# digital_warrior_v02.net
KiCad netlist of a schematic drawn in EAGLE
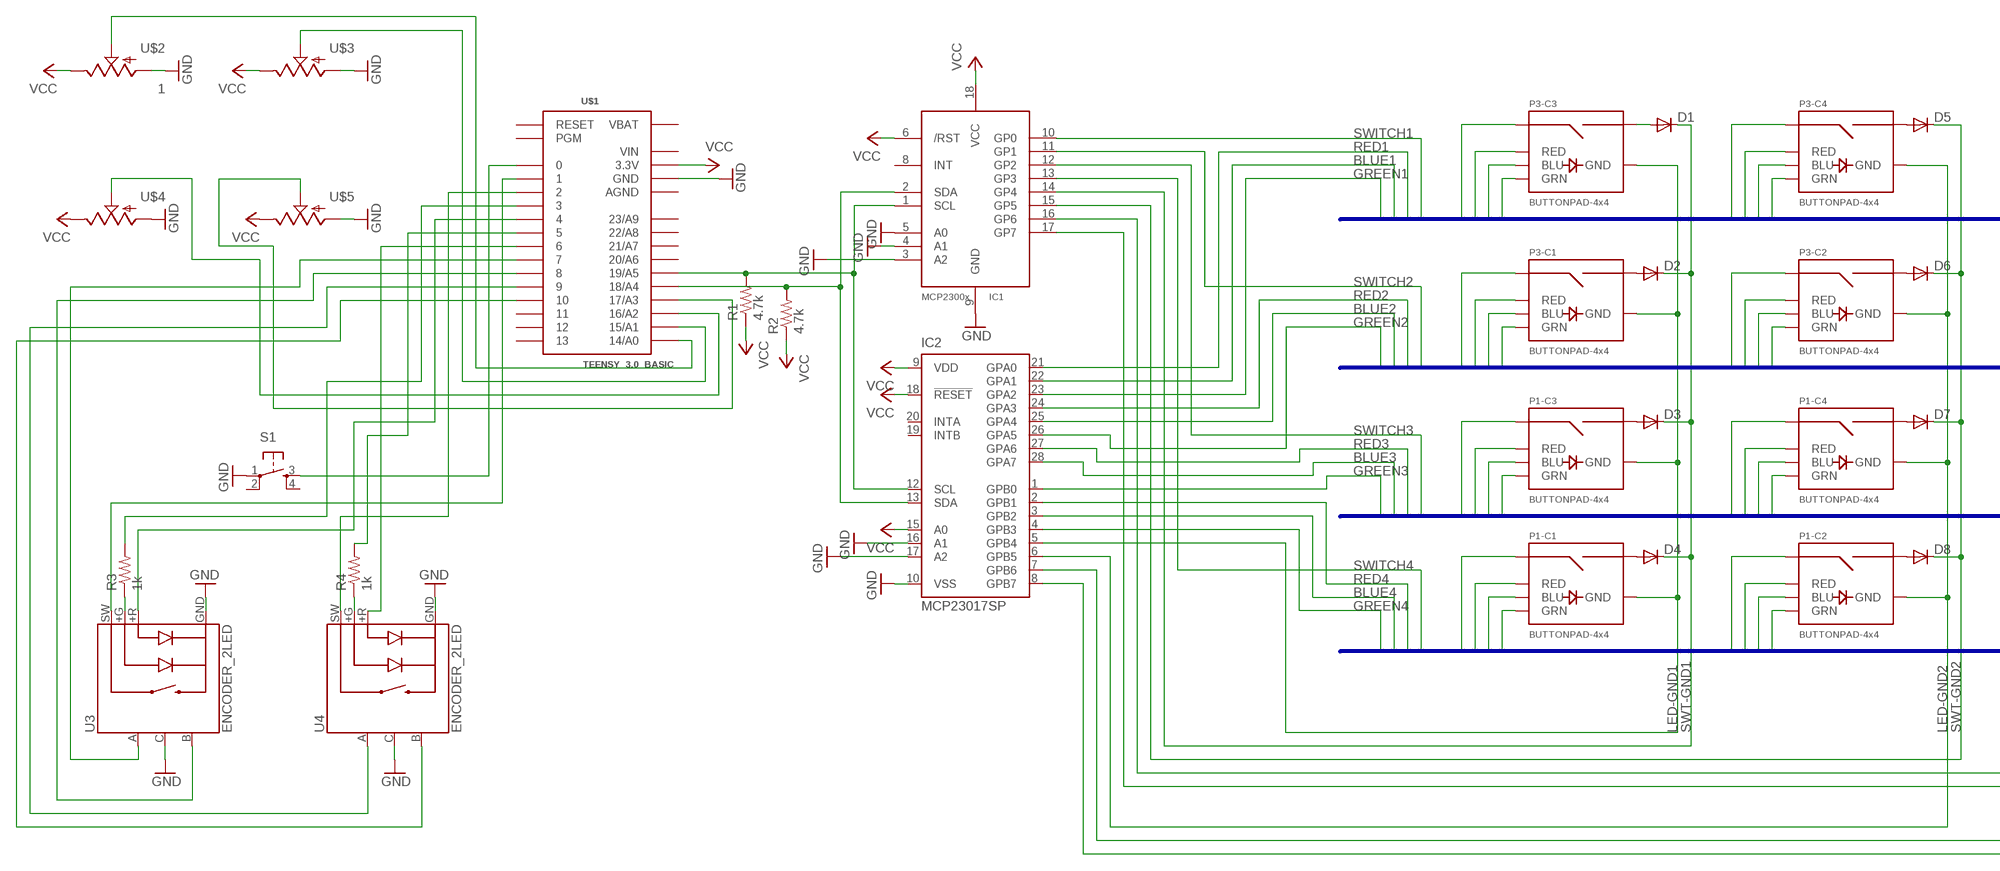
[diagram p0: schematic, sheet 1, part 1 of 2]
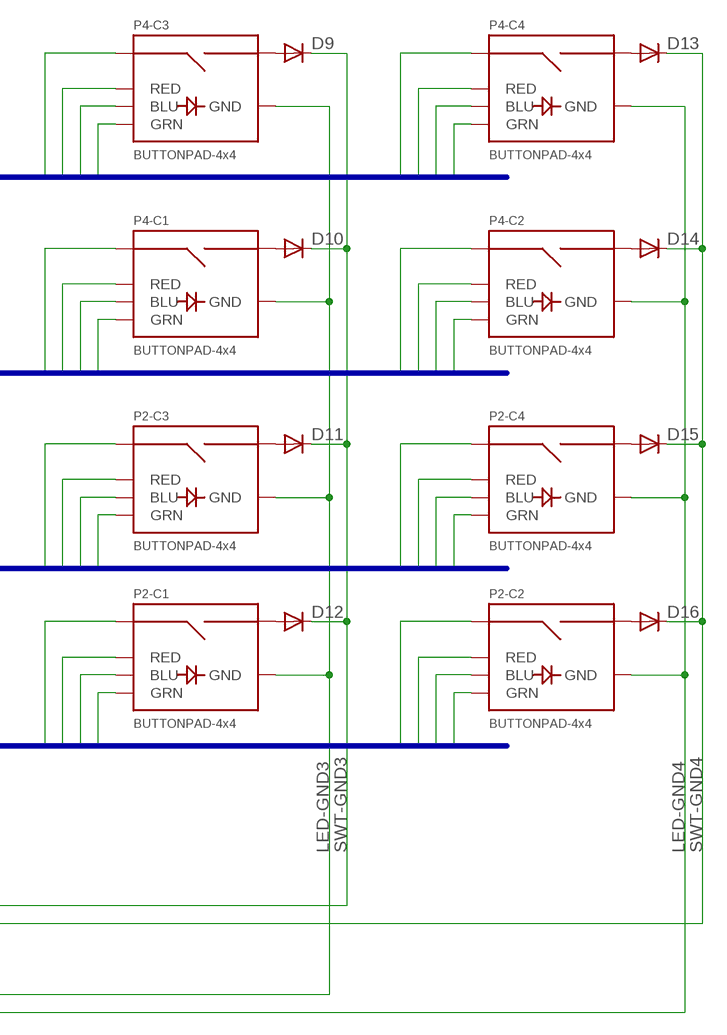
[diagram p1: schematic, sheet 1, part 2 of 2]

(export (version "E")
  (design (tool "Eeschema 10.0.6"))
  (components
    (comp (ref "D1")
      (value "DIODE-1N4148")
      (footprint "eagle-import:DOIDE-1N4148")
      (libsource (lib "eagle-import") (part "DIODE-1N4148"))
    )
    (comp (ref "D2")
      (value "DIODE-1N4148")
      (footprint "eagle-import:DOIDE-1N4148")
      (libsource (lib "eagle-import") (part "DIODE-1N4148"))
    )
    (comp (ref "D3")
      (value "DIODE-1N4148")
      (footprint "eagle-import:DOIDE-1N4148")
      (libsource (lib "eagle-import") (part "DIODE-1N4148"))
    )
    (comp (ref "D4")
      (value "DIODE-1N4148")
      (footprint "eagle-import:DOIDE-1N4148")
      (libsource (lib "eagle-import") (part "DIODE-1N4148"))
    )
    (comp (ref "D5")
      (value "DIODE-1N4148")
      (footprint "eagle-import:DOIDE-1N4148")
      (libsource (lib "eagle-import") (part "DIODE-1N4148"))
    )
    (comp (ref "D6")
      (value "DIODE-1N4148")
      (footprint "eagle-import:DOIDE-1N4148")
      (libsource (lib "eagle-import") (part "DIODE-1N4148"))
    )
    (comp (ref "D7")
      (value "DIODE-1N4148")
      (footprint "eagle-import:DOIDE-1N4148")
      (libsource (lib "eagle-import") (part "DIODE-1N4148"))
    )
    (comp (ref "D8")
      (value "DIODE-1N4148")
      (footprint "eagle-import:DOIDE-1N4148")
      (libsource (lib "eagle-import") (part "DIODE-1N4148"))
    )
    (comp (ref "D9")
      (value "DIODE-1N4148")
      (footprint "eagle-import:DOIDE-1N4148")
      (libsource (lib "eagle-import") (part "DIODE-1N4148"))
    )
    (comp (ref "D10")
      (value "DIODE-1N4148")
      (footprint "eagle-import:DOIDE-1N4148")
      (libsource (lib "eagle-import") (part "DIODE-1N4148"))
    )
    (comp (ref "D11")
      (value "DIODE-1N4148")
      (footprint "eagle-import:DOIDE-1N4148")
      (libsource (lib "eagle-import") (part "DIODE-1N4148"))
    )
    (comp (ref "D12")
      (value "DIODE-1N4148")
      (footprint "eagle-import:DOIDE-1N4148")
      (libsource (lib "eagle-import") (part "DIODE-1N4148"))
    )
    (comp (ref "D13")
      (value "DIODE-1N4148")
      (footprint "eagle-import:DOIDE-1N4148")
      (libsource (lib "eagle-import") (part "DIODE-1N4148"))
    )
    (comp (ref "D14")
      (value "DIODE-1N4148")
      (footprint "eagle-import:DOIDE-1N4148")
      (libsource (lib "eagle-import") (part "DIODE-1N4148"))
    )
    (comp (ref "D15")
      (value "DIODE-1N4148")
      (footprint "eagle-import:DOIDE-1N4148")
      (libsource (lib "eagle-import") (part "DIODE-1N4148"))
    )
    (comp (ref "D16")
      (value "DIODE-1N4148")
      (footprint "eagle-import:DOIDE-1N4148")
      (libsource (lib "eagle-import") (part "DIODE-1N4148"))
    )
    (comp (ref "IC1")
      (value "MCP2300X/P")
      (footprint "eagle-import:DIL18")
      (libsource (lib "eagle-import") (part "MCP2300X/P"))
    )
    (comp (ref "IC2")
      (value "MCP23017SP")
      (footprint "eagle-import:DIL28-3")
      (libsource (lib "eagle-import") (part "MCP23017SP"))
    )
    (comp (ref "P1")
      (value "BUTTONPAD-4x4")
      (footprint "eagle-import:BUTTONPAD-2X2")
      (libsource (lib "eagle-import") (part "BUTTONPAD-2X2"))
    )
    (comp (ref "P2")
      (value "BUTTONPAD-4x4")
      (footprint "eagle-import:BUTTONPAD-2X2")
      (libsource (lib "eagle-import") (part "BUTTONPAD-2X2"))
    )
    (comp (ref "P3")
      (value "BUTTONPAD-4x4")
      (footprint "eagle-import:BUTTONPAD-2X2")
      (libsource (lib "eagle-import") (part "BUTTONPAD-2X2"))
    )
    (comp (ref "P4")
      (value "BUTTONPAD-4x4")
      (footprint "eagle-import:BUTTONPAD-2X2")
      (libsource (lib "eagle-import") (part "BUTTONPAD-2X2"))
    )
    (comp (ref "R1")
      (value "4.7k")
      (footprint "eagle-import:AXIAL-0.4")
      (libsource (lib "eagle-import") (part "RESISTORPTH-1/4W"))
    )
    (comp (ref "R2")
      (value "4.7k")
      (footprint "eagle-import:AXIAL-0.4")
      (libsource (lib "eagle-import") (part "RESISTORPTH-1/4W"))
    )
    (comp (ref "R3")
      (value "1k")
      (footprint "eagle-import:AXIAL-0.4")
      (libsource (lib "eagle-import") (part "SparkFun-Resistors_RESISTORPTH-1/4W"))
    )
    (comp (ref "R4")
      (value "1k")
      (footprint "eagle-import:AXIAL-0.4")
      (libsource (lib "eagle-import") (part "SparkFun-Resistors_RESISTORPTH-1/4W"))
    )
    (comp (ref "S1")
      (value "TAC_SWITCHPTH")
      (footprint "eagle-import:TACTILE-PTH")
      (libsource (lib "eagle-import") (part "TAC_SWITCHPTH"))
    )
    (comp (ref "U$1")
      (value "TEENSY_3.0_BASIC")
      (footprint "eagle-import:TEENSY_3.0_BASIC")
      (libsource (lib "eagle-import") (part "TEENSY_3.0_BASIC"))
    )
    (comp (ref "U$2")
      (value "1")
      (footprint "eagle-import:ALPS_POT")
      (libsource (lib "eagle-import") (part "POT"))
    )
    (comp (ref "U$3")
      (value "POT")
      (footprint "eagle-import:ALPS_POT")
      (libsource (lib "eagle-import") (part "POT"))
    )
    (comp (ref "U$4")
      (value "POT")
      (footprint "eagle-import:ALPS_POT")
      (libsource (lib "eagle-import") (part "POT"))
    )
    (comp (ref "U$5")
      (value "POT")
      (footprint "eagle-import:ALPS_POT")
      (libsource (lib "eagle-import") (part "POT"))
    )
    (comp (ref "U3")
      (value "ENCODER_2LED")
      (footprint "eagle-import:ENCODER_LED_2")
      (libsource (lib "eagle-import") (part "ENCODER_2LED"))
    )
    (comp (ref "U4")
      (value "ENCODER_2LED")
      (footprint "eagle-import:ENCODER_LED_2")
      (libsource (lib "eagle-import") (part "ENCODER_2LED"))
    )
  )
  (nets
    (net (code "1") (name "/AGND") (class "Default")
      (node (ref "U$1") (pin "AGND") (pinfunction "AGND_AGND") (pintype "power_in"))
    )
    (net (code "2") (name "/BLUE1") (class "Default")
      (node (ref "IC2") (pin "22") (pinfunction "GPA1_22") (pintype "bidirectional"))
      (node (ref "P3") (pin "BLU3") (pinfunction "BLU_BLU3") (pintype "bidirectional"))
      (node (ref "P3") (pin "BLU4") (pinfunction "BLU_BLU4") (pintype "bidirectional"))
      (node (ref "P4") (pin "BLU3") (pinfunction "BLU_BLU3") (pintype "bidirectional"))
      (node (ref "P4") (pin "BLU4") (pinfunction "BLU_BLU4") (pintype "bidirectional"))
    )
    (net (code "3") (name "/BLUE2") (class "Default")
      (node (ref "IC2") (pin "25") (pinfunction "GPA4_25") (pintype "bidirectional"))
      (node (ref "P3") (pin "BLU1") (pinfunction "BLU_BLU1") (pintype "bidirectional"))
      (node (ref "P3") (pin "BLU2") (pinfunction "BLU_BLU2") (pintype "bidirectional"))
      (node (ref "P4") (pin "BLU1") (pinfunction "BLU_BLU1") (pintype "bidirectional"))
      (node (ref "P4") (pin "BLU2") (pinfunction "BLU_BLU2") (pintype "bidirectional"))
    )
    (net (code "4") (name "/BLUE3") (class "Default")
      (node (ref "IC2") (pin "28") (pinfunction "GPA7_28") (pintype "bidirectional"))
      (node (ref "P1") (pin "BLU3") (pinfunction "BLU_BLU3") (pintype "bidirectional"))
      (node (ref "P1") (pin "BLU4") (pinfunction "BLU_BLU4") (pintype "bidirectional"))
      (node (ref "P2") (pin "BLU3") (pinfunction "BLU_BLU3") (pintype "bidirectional"))
      (node (ref "P2") (pin "BLU4") (pinfunction "BLU_BLU4") (pintype "bidirectional"))
    )
    (net (code "5") (name "/BLUE4") (class "Default")
      (node (ref "IC2") (pin "3") (pinfunction "GPB2_3") (pintype "bidirectional"))
      (node (ref "P1") (pin "BLU1") (pinfunction "BLU_BLU1") (pintype "bidirectional"))
      (node (ref "P1") (pin "BLU2") (pinfunction "BLU_BLU2") (pintype "bidirectional"))
      (node (ref "P2") (pin "BLU1") (pinfunction "BLU_BLU1") (pintype "bidirectional"))
      (node (ref "P2") (pin "BLU2") (pinfunction "BLU_BLU2") (pintype "bidirectional"))
    )
    (net (code "6") (name "/GREEN1") (class "Default")
      (node (ref "IC2") (pin "23") (pinfunction "GPA2_23") (pintype "bidirectional"))
      (node (ref "P3") (pin "GRN3") (pinfunction "GRN_GRN3") (pintype "bidirectional"))
      (node (ref "P3") (pin "GRN4") (pinfunction "GRN_GRN4") (pintype "bidirectional"))
      (node (ref "P4") (pin "GRN3") (pinfunction "GRN_GRN3") (pintype "bidirectional"))
      (node (ref "P4") (pin "GRN4") (pinfunction "GRN_GRN4") (pintype "bidirectional"))
    )
    (net (code "7") (name "/GREEN2") (class "Default")
      (node (ref "IC2") (pin "26") (pinfunction "GPA5_26") (pintype "bidirectional"))
      (node (ref "P3") (pin "GRN1") (pinfunction "GRN_GRN1") (pintype "bidirectional"))
      (node (ref "P3") (pin "GRN2") (pinfunction "GRN_GRN2") (pintype "bidirectional"))
      (node (ref "P4") (pin "GRN1") (pinfunction "GRN_GRN1") (pintype "bidirectional"))
      (node (ref "P4") (pin "GRN2") (pinfunction "GRN_GRN2") (pintype "bidirectional"))
    )
    (net (code "8") (name "/GREEN3") (class "Default")
      (node (ref "IC2") (pin "1") (pinfunction "GPB0_1") (pintype "bidirectional"))
      (node (ref "P1") (pin "GRN3") (pinfunction "GRN_GRN3") (pintype "bidirectional"))
      (node (ref "P1") (pin "GRN4") (pinfunction "GRN_GRN4") (pintype "bidirectional"))
      (node (ref "P2") (pin "GRN3") (pinfunction "GRN_GRN3") (pintype "bidirectional"))
      (node (ref "P2") (pin "GRN4") (pinfunction "GRN_GRN4") (pintype "bidirectional"))
    )
    (net (code "9") (name "/GREEN4") (class "Default")
      (node (ref "IC2") (pin "4") (pinfunction "GPB3_4") (pintype "bidirectional"))
      (node (ref "P1") (pin "GRN1") (pinfunction "GRN_GRN1") (pintype "bidirectional"))
      (node (ref "P1") (pin "GRN2") (pinfunction "GRN_GRN2") (pintype "bidirectional"))
      (node (ref "P2") (pin "GRN1") (pinfunction "GRN_GRN1") (pintype "bidirectional"))
      (node (ref "P2") (pin "GRN2") (pinfunction "GRN_GRN2") (pintype "bidirectional"))
    )
    (net (code "10") (name "/LED-GND1") (class "Default")
      (node (ref "IC2") (pin "5") (pinfunction "GPB4_5") (pintype "bidirectional"))
      (node (ref "P1") (pin "GND1") (pinfunction "GND_GND1") (pintype "bidirectional"))
      (node (ref "P1") (pin "GND3") (pinfunction "GND_GND3") (pintype "bidirectional"))
      (node (ref "P3") (pin "GND1") (pinfunction "GND_GND1") (pintype "bidirectional"))
      (node (ref "P3") (pin "GND3") (pinfunction "GND_GND3") (pintype "bidirectional"))
    )
    (net (code "11") (name "/LED-GND2") (class "Default")
      (node (ref "IC2") (pin "6") (pinfunction "GPB5_6") (pintype "bidirectional"))
      (node (ref "P1") (pin "GND2") (pinfunction "GND_GND2") (pintype "bidirectional"))
      (node (ref "P1") (pin "GND4") (pinfunction "GND_GND4") (pintype "bidirectional"))
      (node (ref "P3") (pin "GND2") (pinfunction "GND_GND2") (pintype "bidirectional"))
      (node (ref "P3") (pin "GND4") (pinfunction "GND_GND4") (pintype "bidirectional"))
    )
    (net (code "12") (name "/LED-GND3") (class "Default")
      (node (ref "IC2") (pin "7") (pinfunction "GPB6_7") (pintype "bidirectional"))
      (node (ref "P2") (pin "GND1") (pinfunction "GND_GND1") (pintype "bidirectional"))
      (node (ref "P2") (pin "GND3") (pinfunction "GND_GND3") (pintype "bidirectional"))
      (node (ref "P4") (pin "GND1") (pinfunction "GND_GND1") (pintype "bidirectional"))
      (node (ref "P4") (pin "GND3") (pinfunction "GND_GND3") (pintype "bidirectional"))
    )
    (net (code "13") (name "/LED-GND4") (class "Default")
      (node (ref "IC2") (pin "8") (pinfunction "GPB7_8") (pintype "bidirectional"))
      (node (ref "P2") (pin "GND2") (pinfunction "GND_GND2") (pintype "bidirectional"))
      (node (ref "P2") (pin "GND4") (pinfunction "GND_GND4") (pintype "bidirectional"))
      (node (ref "P4") (pin "GND2") (pinfunction "GND_GND2") (pintype "bidirectional"))
      (node (ref "P4") (pin "GND4") (pinfunction "GND_GND4") (pintype "bidirectional"))
    )
    (net (code "14") (name "/RED1") (class "Default")
      (node (ref "IC2") (pin "21") (pinfunction "GPA0_21") (pintype "bidirectional"))
      (node (ref "P3") (pin "RED3") (pinfunction "RED_RED3") (pintype "bidirectional"))
      (node (ref "P3") (pin "RED4") (pinfunction "RED_RED4") (pintype "bidirectional"))
      (node (ref "P4") (pin "RED3") (pinfunction "RED_RED3") (pintype "bidirectional"))
      (node (ref "P4") (pin "RED4") (pinfunction "RED_RED4") (pintype "bidirectional"))
    )
    (net (code "15") (name "/RED2") (class "Default")
      (node (ref "IC2") (pin "24") (pinfunction "GPA3_24") (pintype "bidirectional"))
      (node (ref "P3") (pin "RED1") (pinfunction "RED_RED1") (pintype "bidirectional"))
      (node (ref "P3") (pin "RED2") (pinfunction "RED_RED2") (pintype "bidirectional"))
      (node (ref "P4") (pin "RED1") (pinfunction "RED_RED1") (pintype "bidirectional"))
      (node (ref "P4") (pin "RED2") (pinfunction "RED_RED2") (pintype "bidirectional"))
    )
    (net (code "16") (name "/RED3") (class "Default")
      (node (ref "IC2") (pin "27") (pinfunction "GPA6_27") (pintype "bidirectional"))
      (node (ref "P1") (pin "RED3") (pinfunction "RED_RED3") (pintype "bidirectional"))
      (node (ref "P1") (pin "RED4") (pinfunction "RED_RED4") (pintype "bidirectional"))
      (node (ref "P2") (pin "RED3") (pinfunction "RED_RED3") (pintype "bidirectional"))
      (node (ref "P2") (pin "RED4") (pinfunction "RED_RED4") (pintype "bidirectional"))
    )
    (net (code "17") (name "/RED4") (class "Default")
      (node (ref "IC2") (pin "2") (pinfunction "GPB1_2") (pintype "bidirectional"))
      (node (ref "P1") (pin "RED1") (pinfunction "RED_RED1") (pintype "bidirectional"))
      (node (ref "P1") (pin "RED2") (pinfunction "RED_RED2") (pintype "bidirectional"))
      (node (ref "P2") (pin "RED1") (pinfunction "RED_RED1") (pintype "bidirectional"))
      (node (ref "P2") (pin "RED2") (pinfunction "RED_RED2") (pintype "bidirectional"))
    )
    (net (code "18") (name "/SWITCH1") (class "Default")
      (node (ref "IC1") (pin "10") (pinfunction "GP0_10") (pintype "bidirectional"))
      (node (ref "P3") (pin "SIG5") (pinfunction "SIG1_SIG5") (pintype "bidirectional"))
      (node (ref "P3") (pin "SIG7") (pinfunction "SIG1_SIG7") (pintype "bidirectional"))
      (node (ref "P4") (pin "SIG5") (pinfunction "SIG1_SIG5") (pintype "bidirectional"))
      (node (ref "P4") (pin "SIG7") (pinfunction "SIG1_SIG7") (pintype "bidirectional"))
    )
    (net (code "19") (name "/SWITCH2") (class "Default")
      (node (ref "IC1") (pin "11") (pinfunction "GP1_11") (pintype "bidirectional"))
      (node (ref "P3") (pin "SIG1") (pinfunction "SIG1_SIG1") (pintype "bidirectional"))
      (node (ref "P3") (pin "SIG3") (pinfunction "SIG1_SIG3") (pintype "bidirectional"))
      (node (ref "P4") (pin "SIG1") (pinfunction "SIG1_SIG1") (pintype "bidirectional"))
      (node (ref "P4") (pin "SIG3") (pinfunction "SIG1_SIG3") (pintype "bidirectional"))
    )
    (net (code "20") (name "/SWITCH3") (class "Default")
      (node (ref "IC1") (pin "12") (pinfunction "GP2_12") (pintype "bidirectional"))
      (node (ref "P1") (pin "SIG5") (pinfunction "SIG1_SIG5") (pintype "bidirectional"))
      (node (ref "P1") (pin "SIG7") (pinfunction "SIG1_SIG7") (pintype "bidirectional"))
      (node (ref "P2") (pin "SIG5") (pinfunction "SIG1_SIG5") (pintype "bidirectional"))
      (node (ref "P2") (pin "SIG7") (pinfunction "SIG1_SIG7") (pintype "bidirectional"))
    )
    (net (code "21") (name "/SWITCH4") (class "Default")
      (node (ref "IC1") (pin "13") (pinfunction "GP3_13") (pintype "bidirectional"))
      (node (ref "P1") (pin "SIG1") (pinfunction "SIG1_SIG1") (pintype "bidirectional"))
      (node (ref "P1") (pin "SIG3") (pinfunction "SIG1_SIG3") (pintype "bidirectional"))
      (node (ref "P2") (pin "SIG1") (pinfunction "SIG1_SIG1") (pintype "bidirectional"))
      (node (ref "P2") (pin "SIG3") (pinfunction "SIG1_SIG3") (pintype "bidirectional"))
    )
    (net (code "22") (name "/SWT-GND1") (class "Default")
      (node (ref "D1") (pin "P$2") (pinfunction "C_P$2") (pintype "passive"))
      (node (ref "D2") (pin "P$2") (pinfunction "C_P$2") (pintype "passive"))
      (node (ref "D3") (pin "P$2") (pinfunction "C_P$2") (pintype "passive"))
      (node (ref "D4") (pin "P$2") (pinfunction "C_P$2") (pintype "passive"))
      (node (ref "IC1") (pin "14") (pinfunction "GP4_14") (pintype "bidirectional"))
    )
    (net (code "23") (name "/SWT-GND2") (class "Default")
      (node (ref "D5") (pin "P$2") (pinfunction "C_P$2") (pintype "passive"))
      (node (ref "D6") (pin "P$2") (pinfunction "C_P$2") (pintype "passive"))
      (node (ref "D7") (pin "P$2") (pinfunction "C_P$2") (pintype "passive"))
      (node (ref "D8") (pin "P$2") (pinfunction "C_P$2") (pintype "passive"))
      (node (ref "IC1") (pin "15") (pinfunction "GP5_15") (pintype "bidirectional"))
    )
    (net (code "24") (name "/SWT-GND3") (class "Default")
      (node (ref "D10") (pin "P$2") (pinfunction "C_P$2") (pintype "passive"))
      (node (ref "D11") (pin "P$2") (pinfunction "C_P$2") (pintype "passive"))
      (node (ref "D12") (pin "P$2") (pinfunction "C_P$2") (pintype "passive"))
      (node (ref "D9") (pin "P$2") (pinfunction "C_P$2") (pintype "passive"))
      (node (ref "IC1") (pin "16") (pinfunction "GP6_16") (pintype "bidirectional"))
    )
    (net (code "25") (name "/SWT-GND4") (class "Default")
      (node (ref "D13") (pin "P$2") (pinfunction "C_P$2") (pintype "passive"))
      (node (ref "D14") (pin "P$2") (pinfunction "C_P$2") (pintype "passive"))
      (node (ref "D15") (pin "P$2") (pinfunction "C_P$2") (pintype "passive"))
      (node (ref "D16") (pin "P$2") (pinfunction "C_P$2") (pintype "passive"))
      (node (ref "IC1") (pin "17") (pinfunction "GP7_17") (pintype "bidirectional"))
    )
    (net (code "26") (name "/VBAT") (class "Default")
      (node (ref "U$1") (pin "VBAT") (pinfunction "VBAT_VBAT") (pintype "power_in"))
    )
    (net (code "27") (name "/VIN") (class "Default")
      (node (ref "U$1") (pin "VIN") (pinfunction "VIN_VIN") (pintype "power_in"))
    )
    (net (code "28") (name "GND") (class "Default")
      (node (ref "IC1") (pin "3") (pinfunction "A2_3") (pintype "input"))
      (node (ref "IC1") (pin "4") (pinfunction "A1_4") (pintype "input"))
      (node (ref "IC1") (pin "5") (pinfunction "A0_5") (pintype "input"))
      (node (ref "IC1") (pin "9") (pinfunction "GND_9") (pintype "power_in"))
      (node (ref "IC2") (pin "10") (pinfunction "VSS_10") (pintype "power_in"))
      (node (ref "IC2") (pin "16") (pinfunction "A1_16") (pintype "input"))
      (node (ref "IC2") (pin "17") (pinfunction "A2_17") (pintype "input"))
      (node (ref "S1") (pin "1") (pinfunction "1_1") (pintype "passive"))
      (node (ref "U$1") (pin "GND") (pinfunction "GND_GND") (pintype "power_in"))
      (node (ref "U$1") (pin "GND1") (pinfunction "GND_GND1") (pintype "power_in"))
      (node (ref "U$2") (pin "P$3") (pinfunction "A_P$3") (pintype "passive"))
      (node (ref "U$3") (pin "P$3") (pinfunction "A_P$3") (pintype "passive"))
      (node (ref "U$4") (pin "P$3") (pinfunction "A_P$3") (pintype "passive"))
      (node (ref "U$5") (pin "P$3") (pinfunction "A_P$3") (pintype "passive"))
      (node (ref "U3") (pin "C") (pinfunction "C_C") (pintype "bidirectional"))
      (node (ref "U3") (pin "GND") (pinfunction "-_GND") (pintype "passive"))
      (node (ref "U4") (pin "C") (pinfunction "C_C") (pintype "bidirectional"))
      (node (ref "U4") (pin "GND") (pinfunction "-_GND") (pintype "passive"))
    )
    (net (code "29") (name "Net-(D1-A)") (class "Default")
      (node (ref "D1") (pin "P$1") (pinfunction "A_P$1") (pintype "passive"))
      (node (ref "P3") (pin "SIG6") (pinfunction "SIG2_SIG6") (pintype "bidirectional"))
    )
    (net (code "30") (name "Net-(D2-A)") (class "Default")
      (node (ref "D2") (pin "P$1") (pinfunction "A_P$1") (pintype "passive"))
      (node (ref "P3") (pin "SIG2") (pinfunction "SIG2_SIG2") (pintype "bidirectional"))
    )
    (net (code "31") (name "Net-(D3-A)") (class "Default")
      (node (ref "D3") (pin "P$1") (pinfunction "A_P$1") (pintype "passive"))
      (node (ref "P1") (pin "SIG6") (pinfunction "SIG2_SIG6") (pintype "bidirectional"))
    )
    (net (code "32") (name "Net-(D4-A)") (class "Default")
      (node (ref "D4") (pin "P$1") (pinfunction "A_P$1") (pintype "passive"))
      (node (ref "P1") (pin "SIG2") (pinfunction "SIG2_SIG2") (pintype "bidirectional"))
    )
    (net (code "33") (name "Net-(D5-A)") (class "Default")
      (node (ref "D5") (pin "P$1") (pinfunction "A_P$1") (pintype "passive"))
      (node (ref "P3") (pin "SIG8") (pinfunction "SIG2_SIG8") (pintype "bidirectional"))
    )
    (net (code "34") (name "Net-(D6-A)") (class "Default")
      (node (ref "D6") (pin "P$1") (pinfunction "A_P$1") (pintype "passive"))
      (node (ref "P3") (pin "SIG4") (pinfunction "SIG2_SIG4") (pintype "bidirectional"))
    )
    (net (code "35") (name "Net-(D7-A)") (class "Default")
      (node (ref "D7") (pin "P$1") (pinfunction "A_P$1") (pintype "passive"))
      (node (ref "P1") (pin "SIG8") (pinfunction "SIG2_SIG8") (pintype "bidirectional"))
    )
    (net (code "36") (name "Net-(D8-A)") (class "Default")
      (node (ref "D8") (pin "P$1") (pinfunction "A_P$1") (pintype "passive"))
      (node (ref "P1") (pin "SIG4") (pinfunction "SIG2_SIG4") (pintype "bidirectional"))
    )
    (net (code "37") (name "Net-(D9-A)") (class "Default")
      (node (ref "D9") (pin "P$1") (pinfunction "A_P$1") (pintype "passive"))
      (node (ref "P4") (pin "SIG6") (pinfunction "SIG2_SIG6") (pintype "bidirectional"))
    )
    (net (code "38") (name "Net-(D10-A)") (class "Default")
      (node (ref "D10") (pin "P$1") (pinfunction "A_P$1") (pintype "passive"))
      (node (ref "P4") (pin "SIG2") (pinfunction "SIG2_SIG2") (pintype "bidirectional"))
    )
    (net (code "39") (name "Net-(D11-A)") (class "Default")
      (node (ref "D11") (pin "P$1") (pinfunction "A_P$1") (pintype "passive"))
      (node (ref "P2") (pin "SIG6") (pinfunction "SIG2_SIG6") (pintype "bidirectional"))
    )
    (net (code "40") (name "Net-(D12-A)") (class "Default")
      (node (ref "D12") (pin "P$1") (pinfunction "A_P$1") (pintype "passive"))
      (node (ref "P2") (pin "SIG2") (pinfunction "SIG2_SIG2") (pintype "bidirectional"))
    )
    (net (code "41") (name "Net-(D13-A)") (class "Default")
      (node (ref "D13") (pin "P$1") (pinfunction "A_P$1") (pintype "passive"))
      (node (ref "P4") (pin "SIG8") (pinfunction "SIG2_SIG8") (pintype "bidirectional"))
    )
    (net (code "42") (name "Net-(D14-A)") (class "Default")
      (node (ref "D14") (pin "P$1") (pinfunction "A_P$1") (pintype "passive"))
      (node (ref "P4") (pin "SIG4") (pinfunction "SIG2_SIG4") (pintype "bidirectional"))
    )
    (net (code "43") (name "Net-(D15-A)") (class "Default")
      (node (ref "D15") (pin "P$1") (pinfunction "A_P$1") (pintype "passive"))
      (node (ref "P2") (pin "SIG8") (pinfunction "SIG2_SIG8") (pintype "bidirectional"))
    )
    (net (code "44") (name "Net-(D16-A)") (class "Default")
      (node (ref "D16") (pin "P$1") (pinfunction "A_P$1") (pintype "passive"))
      (node (ref "P2") (pin "SIG4") (pinfunction "SIG2_SIG4") (pintype "bidirectional"))
    )
    (net (code "45") (name "Net-(IC1-SCL)") (class "Default")
      (node (ref "IC1") (pin "1") (pinfunction "SCL_1") (pintype "bidirectional"))
      (node (ref "IC2") (pin "12") (pinfunction "SCL_12") (pintype "input"))
      (node (ref "R1") (pin "P$2") (pinfunction "2_P$2") (pintype "passive"))
      (node (ref "U$1") (pin "19/A5") (pinfunction "19/A5_19/A5") (pintype "bidirectional"))
    )
    (net (code "46") (name "Net-(IC1-SDA)") (class "Default")
      (node (ref "IC1") (pin "2") (pinfunction "SDA_2") (pintype "bidirectional"))
      (node (ref "IC2") (pin "13") (pinfunction "SDA_13") (pintype "bidirectional"))
      (node (ref "R2") (pin "P$2") (pinfunction "2_P$2") (pintype "passive"))
      (node (ref "U$1") (pin "18/A4") (pinfunction "18/A4_18/A4") (pintype "bidirectional"))
    )
    (net (code "47") (name "Net-(R3-1)") (class "Default")
      (node (ref "R3") (pin "P$1") (pinfunction "1_P$1") (pintype "passive"))
      (node (ref "U3") (pin "+G") (pinfunction "+G_+G") (pintype "passive"))
    )
    (net (code "48") (name "Net-(R3-2)") (class "Default")
      (node (ref "R3") (pin "P$2") (pinfunction "2_P$2") (pintype "passive"))
      (node (ref "U$1") (pin "3") (pinfunction "3_3") (pintype "bidirectional"))
    )
    (net (code "49") (name "Net-(R4-1)") (class "Default")
      (node (ref "R4") (pin "P$1") (pinfunction "1_P$1") (pintype "passive"))
      (node (ref "U4") (pin "+G") (pinfunction "+G_+G") (pintype "passive"))
    )
    (net (code "50") (name "Net-(R4-2)") (class "Default")
      (node (ref "R4") (pin "P$2") (pinfunction "2_P$2") (pintype "passive"))
      (node (ref "U$1") (pin "5") (pinfunction "5_5") (pintype "bidirectional"))
    )
    (net (code "51") (name "Net-(S1-Pad3)") (class "Default")
      (node (ref "S1") (pin "3") (pinfunction "3_3") (pintype "passive"))
      (node (ref "U$1") (pin "0") (pinfunction "0_0") (pintype "bidirectional"))
    )
    (net (code "52") (name "Net-(U$1-Pad1)") (class "Default")
      (node (ref "U$1") (pin "1") (pinfunction "1_1") (pintype "bidirectional"))
      (node (ref "U3") (pin "SW") (pinfunction "SW_SW") (pintype "passive"))
    )
    (net (code "53") (name "Net-(U$1-Pad2)") (class "Default")
      (node (ref "U$1") (pin "2") (pinfunction "2_2") (pintype "bidirectional"))
      (node (ref "U4") (pin "SW") (pinfunction "SW_SW") (pintype "passive"))
    )
    (net (code "54") (name "Net-(U$1-Pad4)") (class "Default")
      (node (ref "U$1") (pin "4") (pinfunction "4_4") (pintype "bidirectional"))
      (node (ref "U3") (pin "+R") (pinfunction "+R_+R") (pintype "passive"))
    )
    (net (code "55") (name "Net-(U$1-Pad6)") (class "Default")
      (node (ref "U$1") (pin "6") (pinfunction "6_6") (pintype "bidirectional"))
      (node (ref "U4") (pin "+R") (pinfunction "+R_+R") (pintype "passive"))
    )
    (net (code "56") (name "Net-(U$1-Pad7)") (class "Default")
      (node (ref "U$1") (pin "7") (pinfunction "7_7") (pintype "bidirectional"))
      (node (ref "U3") (pin "A") (pinfunction "A_A") (pintype "bidirectional"))
    )
    (net (code "57") (name "Net-(U$1-Pad8)") (class "Default")
      (node (ref "U$1") (pin "8") (pinfunction "8_8") (pintype "bidirectional"))
      (node (ref "U3") (pin "B") (pinfunction "B_B") (pintype "bidirectional"))
    )
    (net (code "58") (name "Net-(U$1-Pad9)") (class "Default")
      (node (ref "U$1") (pin "9") (pinfunction "9_9") (pintype "bidirectional"))
      (node (ref "U4") (pin "A") (pinfunction "A_A") (pintype "bidirectional"))
    )
    (net (code "59") (name "Net-(U$1-Pad10)") (class "Default")
      (node (ref "U$1") (pin "10") (pinfunction "10_10") (pintype "bidirectional"))
      (node (ref "U4") (pin "B") (pinfunction "B_B") (pintype "bidirectional"))
    )
    (net (code "60") (name "Net-(U$2-S)") (class "Default")
      (node (ref "U$1") (pin "14/A0") (pinfunction "14/A0_14/A0") (pintype "bidirectional"))
      (node (ref "U$2") (pin "P$2") (pinfunction "S_P$2") (pintype "passive"))
    )
    (net (code "61") (name "Net-(U$3-S)") (class "Default")
      (node (ref "U$1") (pin "15/A1") (pinfunction "15/A1_15/A1") (pintype "bidirectional"))
      (node (ref "U$3") (pin "P$2") (pinfunction "S_P$2") (pintype "passive"))
    )
    (net (code "62") (name "Net-(U$4-S)") (class "Default")
      (node (ref "U$1") (pin "16/A2") (pinfunction "16/A2_16/A2") (pintype "bidirectional"))
      (node (ref "U$4") (pin "P$2") (pinfunction "S_P$2") (pintype "passive"))
    )
    (net (code "63") (name "Net-(U$5-S)") (class "Default")
      (node (ref "U$1") (pin "17/A3") (pinfunction "17/A3_17/A3") (pintype "bidirectional"))
      (node (ref "U$5") (pin "P$2") (pinfunction "S_P$2") (pintype "passive"))
    )
    (net (code "64") (name "VCC") (class "Default")
      (node (ref "IC1") (pin "18") (pinfunction "VCC_18") (pintype "power_in"))
      (node (ref "IC1") (pin "6") (pinfunction "/RST_6") (pintype "input"))
      (node (ref "IC2") (pin "15") (pinfunction "A0_15") (pintype "input"))
      (node (ref "IC2") (pin "18") (pinfunction "~{RESET}_18") (pintype "input"))
      (node (ref "IC2") (pin "9") (pinfunction "VDD_9") (pintype "power_in"))
      (node (ref "R1") (pin "P$1") (pinfunction "1_P$1") (pintype "passive"))
      (node (ref "R2") (pin "P$1") (pinfunction "1_P$1") (pintype "passive"))
      (node (ref "U$1") (pin "3.3V") (pinfunction "3.3V_3.3V") (pintype "power_in"))
      (node (ref "U$1") (pin "3.3V1") (pinfunction "3.3V_3.3V1") (pintype "power_in"))
      (node (ref "U$2") (pin "P$1") (pinfunction "E_P$1") (pintype "passive"))
      (node (ref "U$3") (pin "P$1") (pinfunction "E_P$1") (pintype "passive"))
      (node (ref "U$4") (pin "P$1") (pinfunction "E_P$1") (pintype "passive"))
      (node (ref "U$5") (pin "P$1") (pinfunction "E_P$1") (pintype "passive"))
    )
    (net (code "65") (name "unconnected-(IC1-INT-Pad8)") (class "Default")
      (node (ref "IC1") (pin "8") (pinfunction "INT_8") (pintype "output"))
    )
    (net (code "66") (name "unconnected-(IC2-INTA-Pad20)") (class "Default")
      (node (ref "IC2") (pin "20") (pinfunction "INTA_20") (pintype "output"))
    )
    (net (code "67") (name "unconnected-(IC2-INTB-Pad19)") (class "Default")
      (node (ref "IC2") (pin "19") (pinfunction "INTB_19") (pintype "output"))
    )
    (net (code "68") (name "unconnected-(S1-Pad2)") (class "Default")
      (node (ref "S1") (pin "2") (pinfunction "2_2") (pintype "passive"))
    )
    (net (code "69") (name "unconnected-(S1-Pad4)") (class "Default")
      (node (ref "S1") (pin "4") (pinfunction "4_4") (pintype "passive"))
    )
    (net (code "70") (name "unconnected-(U$1-Pad11)") (class "Default")
      (node (ref "U$1") (pin "11") (pinfunction "11_11") (pintype "bidirectional"))
    )
    (net (code "71") (name "unconnected-(U$1-Pad12)") (class "Default")
      (node (ref "U$1") (pin "12") (pinfunction "12_12") (pintype "bidirectional"))
    )
    (net (code "72") (name "unconnected-(U$1-Pad13)") (class "Default")
      (node (ref "U$1") (pin "13") (pinfunction "13_13") (pintype "bidirectional"))
    )
    (net (code "73") (name "unconnected-(U$1-Pad20{slash}A6)") (class "Default")
      (node (ref "U$1") (pin "20/A6") (pinfunction "20/A6_20/A6") (pintype "bidirectional"))
    )
    (net (code "74") (name "unconnected-(U$1-Pad21{slash}A7)") (class "Default")
      (node (ref "U$1") (pin "21/A7") (pinfunction "21/A7_21/A7") (pintype "bidirectional"))
    )
    (net (code "75") (name "unconnected-(U$1-Pad22{slash}A8)") (class "Default")
      (node (ref "U$1") (pin "22/A8") (pinfunction "22/A8_22/A8") (pintype "bidirectional"))
    )
    (net (code "76") (name "unconnected-(U$1-Pad23{slash}A9)") (class "Default")
      (node (ref "U$1") (pin "23/A9") (pinfunction "23/A9_23/A9") (pintype "bidirectional"))
    )
    (net (code "77") (name "unconnected-(U$1-PadPGM)") (class "Default")
      (node (ref "U$1") (pin "PGM") (pinfunction "PGM_PGM") (pintype "bidirectional"))
    )
    (net (code "78") (name "unconnected-(U$1-PadRESET)") (class "Default")
      (node (ref "U$1") (pin "RESET") (pinfunction "RESET_RESET") (pintype "bidirectional"))
    )
  )
)
